# mood_ring.net
KiCad netlist of a schematic drawn in EAGLE
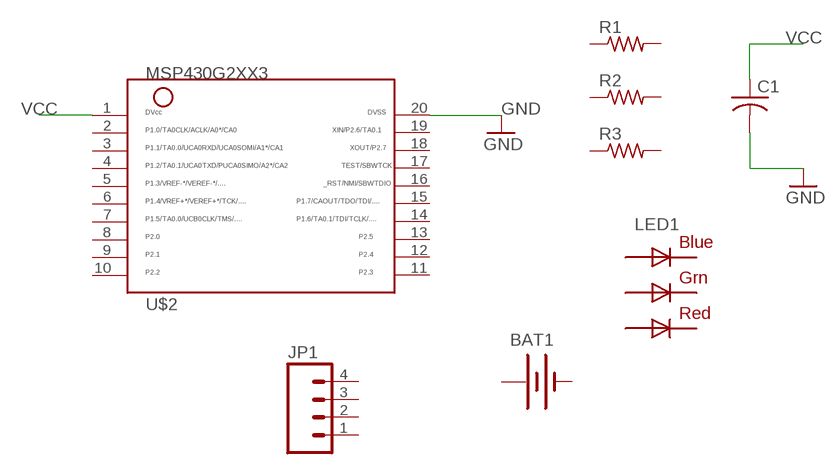
[diagram p0: schematic, sheet 1]

(export (version "E")
  (design (tool "Eeschema 10.0.6"))
  (components
    (comp (ref "BAT1")
      (value "BATTERYBU2032SM")
      (footprint "eagle-import:BU2032SM")
      (libsource (lib "eagle-import") (part "BATTERYBU2032SM"))
    )
    (comp (ref "C1")
      (value "C-USC1206")
      (footprint "eagle-import:C1206")
      (libsource (lib "eagle-import") (part "C-USC1206"))
    )
    (comp (ref "JP1")
      (value "M04LOCK")
      (footprint "eagle-import:1X04_LOCK")
      (libsource (lib "eagle-import") (part "M04LOCK"))
    )
    (comp (ref "LED1")
      (value "RGBLED5050")
      (footprint "eagle-import:RGBLED5050")
      (libsource (lib "eagle-import") (part "RGBLED5050"))
    )
    (comp (ref "R1")
      (value "R-US_R1206")
      (footprint "eagle-import:R1206")
      (libsource (lib "eagle-import") (part "R-US_R1206"))
    )
    (comp (ref "R2")
      (value "R-US_R1206")
      (footprint "eagle-import:R1206")
      (libsource (lib "eagle-import") (part "R-US_R1206"))
    )
    (comp (ref "R3")
      (value "R-US_R1206")
      (footprint "eagle-import:R1206")
      (libsource (lib "eagle-import") (part "R-US_R1206"))
    )
    (comp (ref "U$2")
      (value "MSP430G2XX3TSSOP")
      (footprint "eagle-import:PW20")
      (libsource (lib "eagle-import") (part "MSP430G2XX3TSSOP"))
    )
  )
  (nets
    (net (code "1") (name "/+") (class "Default")
      (node (ref "BAT1") (pin "P$1") (pinfunction "+_P$1") (pintype "power_in"))
    )
    (net (code "2") (name "/-") (class "Default")
      (node (ref "BAT1") (pin "P$2") (pinfunction "-_P$2") (pintype "power_in"))
    )
    (net (code "3") (name "/VCC") (class "Default")
      (node (ref "C1") (pin "1") (pinfunction "1_1") (pintype "passive"))
      (node (ref "U$2") (pin "1") (pinfunction "1_1") (pintype "bidirectional"))
    )
    (net (code "4") (name "GND") (class "Default")
      (node (ref "C1") (pin "2") (pinfunction "2_2") (pintype "passive"))
      (node (ref "U$2") (pin "20") (pinfunction "20_20") (pintype "bidirectional"))
    )
    (net (code "5") (name "unconnected-(JP1-Pad1)") (class "Default")
      (node (ref "JP1") (pin "1") (pinfunction "1_1") (pintype "passive"))
    )
    (net (code "6") (name "unconnected-(JP1-Pad2)") (class "Default")
      (node (ref "JP1") (pin "2") (pinfunction "2_2") (pintype "passive"))
    )
    (net (code "7") (name "unconnected-(JP1-Pad3)") (class "Default")
      (node (ref "JP1") (pin "3") (pinfunction "3_3") (pintype "passive"))
    )
    (net (code "8") (name "unconnected-(JP1-Pad4)") (class "Default")
      (node (ref "JP1") (pin "4") (pinfunction "4_4") (pintype "passive"))
    )
    (net (code "9") (name "unconnected-(LED1-BLUE_A-Pad3)") (class "Default")
      (node (ref "LED1") (pin "3") (pinfunction "BLUE_A_3") (pintype "bidirectional"))
    )
    (net (code "10") (name "unconnected-(LED1-BLUE_C-Pad4)") (class "Default")
      (node (ref "LED1") (pin "4") (pinfunction "BLUE_C_4") (pintype "bidirectional"))
    )
    (net (code "11") (name "unconnected-(LED1-GREEN_A-Pad1)") (class "Default")
      (node (ref "LED1") (pin "1") (pinfunction "GREEN_A_1") (pintype "bidirectional"))
    )
    (net (code "12") (name "unconnected-(LED1-GREEN_C-Pad6)") (class "Default")
      (node (ref "LED1") (pin "6") (pinfunction "GREEN_C_6") (pintype "bidirectional"))
    )
    (net (code "13") (name "unconnected-(LED1-RED_A-Pad2)") (class "Default")
      (node (ref "LED1") (pin "2") (pinfunction "RED_A_2") (pintype "bidirectional"))
    )
    (net (code "14") (name "unconnected-(LED1-RED_C-Pad5)") (class "Default")
      (node (ref "LED1") (pin "5") (pinfunction "RED_C_5") (pintype "bidirectional"))
    )
    (net (code "15") (name "unconnected-(R1-Pad1)") (class "Default")
      (node (ref "R1") (pin "1") (pinfunction "1_1") (pintype "passive"))
    )
    (net (code "16") (name "unconnected-(R1-Pad2)") (class "Default")
      (node (ref "R1") (pin "2") (pinfunction "2_2") (pintype "passive"))
    )
    (net (code "17") (name "unconnected-(R2-Pad1)") (class "Default")
      (node (ref "R2") (pin "1") (pinfunction "1_1") (pintype "passive"))
    )
    (net (code "18") (name "unconnected-(R2-Pad2)") (class "Default")
      (node (ref "R2") (pin "2") (pinfunction "2_2") (pintype "passive"))
    )
    (net (code "19") (name "unconnected-(R3-Pad1)") (class "Default")
      (node (ref "R3") (pin "1") (pinfunction "1_1") (pintype "passive"))
    )
    (net (code "20") (name "unconnected-(R3-Pad2)") (class "Default")
      (node (ref "R3") (pin "2") (pinfunction "2_2") (pintype "passive"))
    )
    (net (code "21") (name "unconnected-(U$2-Pad2)") (class "Default")
      (node (ref "U$2") (pin "2") (pinfunction "2_2") (pintype "bidirectional"))
    )
    (net (code "22") (name "unconnected-(U$2-Pad3)") (class "Default")
      (node (ref "U$2") (pin "3") (pinfunction "3_3") (pintype "bidirectional"))
    )
    (net (code "23") (name "unconnected-(U$2-Pad4)") (class "Default")
      (node (ref "U$2") (pin "4") (pinfunction "4_4") (pintype "bidirectional"))
    )
    (net (code "24") (name "unconnected-(U$2-Pad5)") (class "Default")
      (node (ref "U$2") (pin "5") (pinfunction "5_5") (pintype "bidirectional"))
    )
    (net (code "25") (name "unconnected-(U$2-Pad6)") (class "Default")
      (node (ref "U$2") (pin "6") (pinfunction "6_6") (pintype "bidirectional"))
    )
    (net (code "26") (name "unconnected-(U$2-Pad7)") (class "Default")
      (node (ref "U$2") (pin "7") (pinfunction "7_7") (pintype "bidirectional"))
    )
    (net (code "27") (name "unconnected-(U$2-Pad8)") (class "Default")
      (node (ref "U$2") (pin "8") (pinfunction "8_8") (pintype "bidirectional"))
    )
    (net (code "28") (name "unconnected-(U$2-Pad9)") (class "Default")
      (node (ref "U$2") (pin "9") (pinfunction "9_9") (pintype "bidirectional"))
    )
    (net (code "29") (name "unconnected-(U$2-Pad10)") (class "Default")
      (node (ref "U$2") (pin "10") (pinfunction "10_10") (pintype "bidirectional"))
    )
    (net (code "30") (name "unconnected-(U$2-Pad11)") (class "Default")
      (node (ref "U$2") (pin "11") (pinfunction "11_11") (pintype "bidirectional"))
    )
    (net (code "31") (name "unconnected-(U$2-Pad12)") (class "Default")
      (node (ref "U$2") (pin "12") (pinfunction "12_12") (pintype "bidirectional"))
    )
    (net (code "32") (name "unconnected-(U$2-Pad13)") (class "Default")
      (node (ref "U$2") (pin "13") (pinfunction "13_13") (pintype "bidirectional"))
    )
    (net (code "33") (name "unconnected-(U$2-Pad14)") (class "Default")
      (node (ref "U$2") (pin "14") (pinfunction "14_14") (pintype "bidirectional"))
    )
    (net (code "34") (name "unconnected-(U$2-Pad15)") (class "Default")
      (node (ref "U$2") (pin "15") (pinfunction "15_15") (pintype "bidirectional"))
    )
    (net (code "35") (name "unconnected-(U$2-Pad16)") (class "Default")
      (node (ref "U$2") (pin "16") (pinfunction "16_16") (pintype "bidirectional"))
    )
    (net (code "36") (name "unconnected-(U$2-Pad17)") (class "Default")
      (node (ref "U$2") (pin "17") (pinfunction "17_17") (pintype "bidirectional"))
    )
    (net (code "37") (name "unconnected-(U$2-Pad18)") (class "Default")
      (node (ref "U$2") (pin "18") (pinfunction "18_18") (pintype "bidirectional"))
    )
    (net (code "38") (name "unconnected-(U$2-Pad19)") (class "Default")
      (node (ref "U$2") (pin "19") (pinfunction "19_19") (pintype "bidirectional"))
    )
  )
)
